# KT-744.net
KiCad netlist of a schematic drawn in EAGLE
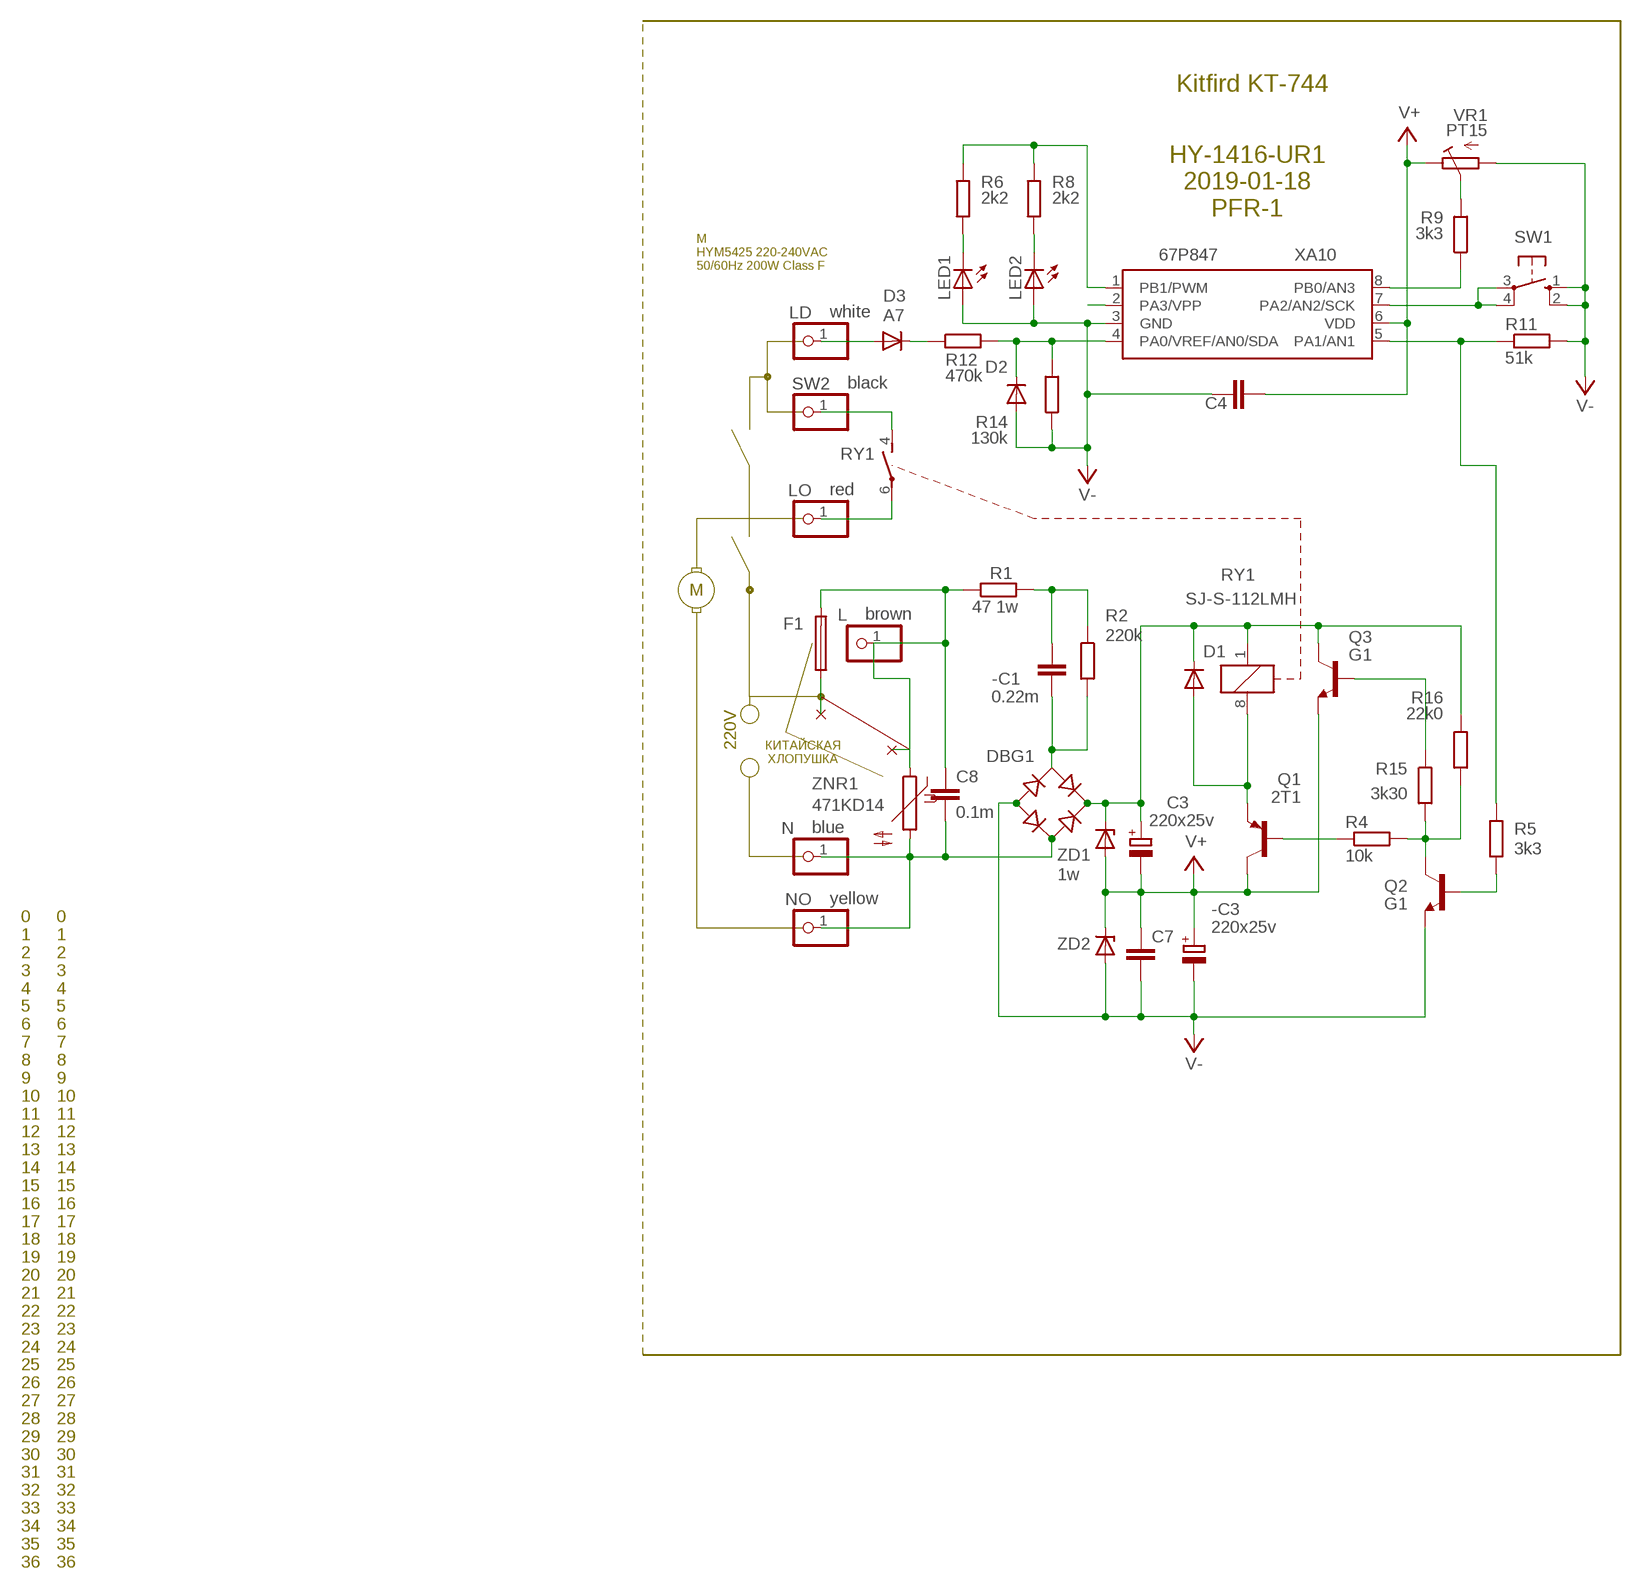
[diagram p0: schematic, sheet 1]

(export (version "E")
  (design (tool "Eeschema 10.0.6"))
  (components
    (comp (ref "-C1")
      (value "0.22m")
      (footprint "eagle-import:C150-072X183")
      (libsource (lib "eagle-import") (part "C-EU150-072X183"))
    )
    (comp (ref "-C3")
      (value "220x25v")
      (footprint "eagle-import:E5-10,5")
      (libsource (lib "eagle-import") (part "CPOL-EUE5-10.5"))
    )
    (comp (ref "67P847")
      (value "XA10")
      (footprint "eagle-import:SOIC8")
      (libsource (lib "eagle-import") (part "SH67P847"))
    )
    (comp (ref "C3")
      (value "220x25v")
      (footprint "eagle-import:E5-10,5")
      (libsource (lib "eagle-import") (part "CPOL-EUE5-10.5"))
    )
    (comp (ref "C4")
      (value "C-EU150-072X183")
      (footprint "eagle-import:C150-072X183")
      (libsource (lib "eagle-import") (part "C-EU150-072X183"))
    )
    (comp (ref "C7")
      (value "C-EU150-072X183")
      (footprint "eagle-import:C150-072X183")
      (libsource (lib "eagle-import") (part "C-EU150-072X183"))
    )
    (comp (ref "C8")
      (value "0.1m")
      (footprint "eagle-import:C102-064X133")
      (libsource (lib "eagle-import") (part "C-EU102-064X133"))
    )
    (comp (ref "D1")
      (value "DIODE-SOD80C")
      (footprint "eagle-import:SOD80C")
      (libsource (lib "eagle-import") (part "DIODE-SOD80C"))
    )
    (comp (ref "D2")
      (value "DIODE-SOD80C")
      (footprint "eagle-import:SOD80C")
      (libsource (lib "eagle-import") (part "DIODE-SOD80C"))
    )
    (comp (ref "D3")
      (value "A7")
      (footprint "eagle-import:SOD80C")
      (libsource (lib "eagle-import") (part "DIODE-SOD80C"))
    )
    (comp (ref "DBG1")
      (value "B1S")
      (footprint "eagle-import:MBS")
      (libsource (lib "eagle-import") (part "BS1"))
    )
    (comp (ref "F1")
      (value "PICOFUSE")
      (footprint "eagle-import:PICOFUSE")
      (libsource (lib "eagle-import") (part "PICOFUSE"))
    )
    (comp (ref "L")
      (value "brown")
      (footprint "eagle-import:1X01")
      (libsource (lib "eagle-import") (part "PINHD-1X1"))
    )
    (comp (ref "LD")
      (value "white")
      (footprint "eagle-import:1X01")
      (libsource (lib "eagle-import") (part "PINHD-1X1"))
    )
    (comp (ref "LED1")
      (value "LEDSML0805")
      (footprint "eagle-import:SML0805")
      (libsource (lib "eagle-import") (part "LEDSML0805"))
    )
    (comp (ref "LED2")
      (value "LEDSML0805")
      (footprint "eagle-import:SML0805")
      (libsource (lib "eagle-import") (part "LEDSML0805"))
    )
    (comp (ref "LO")
      (value "red")
      (footprint "eagle-import:1X01")
      (libsource (lib "eagle-import") (part "PINHD-1X1"))
    )
    (comp (ref "N")
      (value "blue")
      (footprint "eagle-import:1X01")
      (libsource (lib "eagle-import") (part "PINHD-1X1"))
    )
    (comp (ref "NO")
      (value "yellow")
      (footprint "eagle-import:1X01")
      (libsource (lib "eagle-import") (part "PINHD-1X1"))
    )
    (comp (ref "Q1")
      (value "2T1")
      (footprint "eagle-import:SOT23-EBC")
      (libsource (lib "eagle-import") (part "-PNP-SOT23-EBC"))
    )
    (comp (ref "Q2")
      (value "G1")
      (footprint "eagle-import:SOT23-EBC")
      (libsource (lib "eagle-import") (part "-NPN-SOT23-EBC"))
    )
    (comp (ref "Q3")
      (value "G1")
      (footprint "eagle-import:SOT23-EBC")
      (libsource (lib "eagle-import") (part "-NPN-SOT23-EBC"))
    )
    (comp (ref "R1")
      (value "47 1w")
      (footprint "eagle-import:0414_15")
      (libsource (lib "eagle-import") (part "R-EU_0414/15"))
    )
    (comp (ref "R2")
      (value "220k")
      (footprint "eagle-import:0207_12")
      (libsource (lib "eagle-import") (part "R-EU_0207/12"))
    )
    (comp (ref "R4")
      (value "10k")
      (footprint "eagle-import:M1206")
      (libsource (lib "eagle-import") (part "R-EU_M1206"))
    )
    (comp (ref "R5")
      (value "3k3")
      (footprint "eagle-import:M0805")
      (libsource (lib "eagle-import") (part "R-EU_M0805"))
    )
    (comp (ref "R6")
      (value "2k2")
      (footprint "eagle-import:0207_12")
      (libsource (lib "eagle-import") (part "R-EU_0207/12"))
    )
    (comp (ref "R8")
      (value "2k2")
      (footprint "eagle-import:0207_12")
      (libsource (lib "eagle-import") (part "R-EU_0207/12"))
    )
    (comp (ref "R9")
      (value "3k3")
      (footprint "eagle-import:M0805")
      (libsource (lib "eagle-import") (part "R-EU_M0805"))
    )
    (comp (ref "R11")
      (value "51k")
      (footprint "eagle-import:M0805")
      (libsource (lib "eagle-import") (part "R-EU_M0805"))
    )
    (comp (ref "R12")
      (value "470k")
      (footprint "eagle-import:0207_15")
      (libsource (lib "eagle-import") (part "R-EU_0207/15"))
    )
    (comp (ref "R14")
      (value "130k")
      (footprint "eagle-import:M0805")
      (libsource (lib "eagle-import") (part "R-EU_M0805"))
    )
    (comp (ref "R15")
      (value "3k30")
      (footprint "eagle-import:M1206")
      (libsource (lib "eagle-import") (part "R-EU_M1206"))
    )
    (comp (ref "R16")
      (value "22k0")
      (footprint "eagle-import:M0805")
      (libsource (lib "eagle-import") (part "R-EU_M0805"))
    )
    (comp (ref "RY1")
      (value "SJ-S-112LMH")
      (footprint "eagle-import:JW1A")
      (libsource (lib "eagle-import") (part "JW1A"))
    )
    (comp (ref "SW1")
      (value "10-XX")
      (footprint "eagle-import:B3F-10XX")
      (fields (field (name "MPN") "B3F-1000"))
      (libsource (lib "eagle-import") (part "10-XX"))
    )
    (comp (ref "SW2")
      (value "black")
      (footprint "eagle-import:1X01")
      (libsource (lib "eagle-import") (part "PINHD-1X1"))
    )
    (comp (ref "VR1")
      (value "PT15")
      (footprint "eagle-import:RTRIM3339P")
      (libsource (lib "eagle-import") (part "R-TRIMM3339P"))
    )
    (comp (ref "ZD1")
      (value "1w")
      (footprint "eagle-import:F126Z10")
      (libsource (lib "eagle-import") (part "ZENER-DIODEF126-10"))
    )
    (comp (ref "ZD2")
      (value "ZENER-DIODEC1702-15")
      (footprint "eagle-import:C1702-15")
      (libsource (lib "eagle-import") (part "ZENER-DIODEC1702-15"))
    )
    (comp (ref "ZNR1")
      (value "471KD14")
      (footprint "eagle-import:S07K17")
      (libsource (lib "eagle-import") (part "S07K17"))
    )
  )
  (nets
    (net (code "1") (name "Net-(-C1-Pad1)") (class "Default")
      (node (ref "-C1") (pin "1") (pinfunction "1_1") (pintype "passive"))
      (node (ref "R1") (pin "2") (pinfunction "2_2") (pintype "passive"))
      (node (ref "R2") (pin "1") (pinfunction "1_1") (pintype "passive"))
    )
    (net (code "2") (name "Net-(-C1-Pad2)") (class "Default")
      (node (ref "-C1") (pin "2") (pinfunction "2_2") (pintype "passive"))
      (node (ref "DBG1") (pin "AC1") (pinfunction "AC1_AC1") (pintype "passive"))
      (node (ref "R2") (pin "2") (pinfunction "2_2") (pintype "passive"))
    )
    (net (code "3") (name "Net-(67P847-PA0{slash}VREF{slash}AN0{slash}SDA)") (class "Default")
      (node (ref "67P847") (pin "4") (pinfunction "PA0/VREF/AN0/SDA_4") (pintype "bidirectional"))
      (node (ref "D2") (pin "C") (pinfunction "C_C") (pintype "passive"))
      (node (ref "R12") (pin "2") (pinfunction "2_2") (pintype "passive"))
      (node (ref "R14") (pin "2") (pinfunction "2_2") (pintype "passive"))
    )
    (net (code "4") (name "Net-(67P847-PA1{slash}AN1)") (class "Default")
      (node (ref "67P847") (pin "5") (pinfunction "PA1/AN1_5") (pintype "bidirectional"))
      (node (ref "R11") (pin "1") (pinfunction "1_1") (pintype "passive"))
      (node (ref "R5") (pin "1") (pinfunction "1_1") (pintype "passive"))
    )
    (net (code "5") (name "Net-(67P847-PA2{slash}AN2{slash}SCK)") (class "Default")
      (node (ref "67P847") (pin "7") (pinfunction "PA2/AN2/SCK_7") (pintype "bidirectional"))
      (node (ref "SW1") (pin "3") (pinfunction "P_3") (pintype "passive"))
      (node (ref "SW1") (pin "4") (pinfunction "P1_4") (pintype "passive"))
    )
    (net (code "6") (name "Net-(67P847-PB0{slash}AN3)") (class "Default")
      (node (ref "67P847") (pin "8") (pinfunction "PB0/AN3_8") (pintype "bidirectional"))
      (node (ref "R9") (pin "1") (pinfunction "1_1") (pintype "passive"))
    )
    (net (code "7") (name "Net-(67P847-PB1{slash}PWM)") (class "Default")
      (node (ref "67P847") (pin "1") (pinfunction "PB1/PWM_1") (pintype "bidirectional"))
      (node (ref "R6") (pin "2") (pinfunction "2_2") (pintype "passive"))
      (node (ref "R8") (pin "2") (pinfunction "2_2") (pintype "passive"))
    )
    (net (code "8") (name "Net-(C3-Pad+)") (class "Default")
      (node (ref "C3") (pin "+") (pinfunction "+_+") (pintype "passive"))
      (node (ref "D1") (pin "C") (pinfunction "C_C") (pintype "passive"))
      (node (ref "DBG1") (pin "+") (pinfunction "+_+") (pintype "passive"))
      (node (ref "Q3") (pin "C") (pinfunction "C_C") (pintype "passive"))
      (node (ref "R16") (pin "1") (pinfunction "1_1") (pintype "passive"))
      (node (ref "RY1") (pin "1") (pinfunction "1_1") (pintype "passive"))
      (node (ref "ZD1") (pin "C") (pinfunction "C_C") (pintype "passive"))
    )
    (net (code "9") (name "Net-(C8-Pad1)") (class "Default")
      (node (ref "C8") (pin "1") (pinfunction "1_1") (pintype "passive"))
      (node (ref "F1") (pin "2") (pinfunction "2_2") (pintype "passive"))
      (node (ref "L") (pin "1") (pinfunction "1_1") (pintype "passive"))
      (node (ref "R1") (pin "1") (pinfunction "1_1") (pintype "passive"))
      (node (ref "ZNR1") (pin "1") (pinfunction "1_1") (pintype "passive"))
    )
    (net (code "10") (name "Net-(C8-Pad2)") (class "Default")
      (node (ref "C8") (pin "2") (pinfunction "2_2") (pintype "passive"))
      (node (ref "DBG1") (pin "AC2") (pinfunction "AC2_AC2") (pintype "passive"))
      (node (ref "N") (pin "1") (pinfunction "1_1") (pintype "passive"))
      (node (ref "NO") (pin "1") (pinfunction "1_1") (pintype "passive"))
      (node (ref "ZNR1") (pin "2") (pinfunction "2_2") (pintype "passive"))
    )
    (net (code "11") (name "Net-(D3-PadA)") (class "Default")
      (node (ref "D3") (pin "A") (pinfunction "A_A") (pintype "passive"))
      (node (ref "LD") (pin "1") (pinfunction "1_1") (pintype "passive"))
    )
    (net (code "12") (name "Net-(D3-PadC)") (class "Default")
      (node (ref "D3") (pin "C") (pinfunction "C_C") (pintype "passive"))
      (node (ref "R12") (pin "1") (pinfunction "1_1") (pintype "passive"))
    )
    (net (code "13") (name "Net-(LED1-PadC)") (class "Default")
      (node (ref "LED1") (pin "C") (pinfunction "C_C") (pintype "passive"))
      (node (ref "R6") (pin "1") (pinfunction "1_1") (pintype "passive"))
    )
    (net (code "14") (name "Net-(LED2-PadC)") (class "Default")
      (node (ref "LED2") (pin "C") (pinfunction "C_C") (pintype "passive"))
      (node (ref "R8") (pin "1") (pinfunction "1_1") (pintype "passive"))
    )
    (net (code "15") (name "Net-(Q1-PadB)") (class "Default")
      (node (ref "Q1") (pin "B") (pinfunction "B_B") (pintype "passive"))
      (node (ref "R4") (pin "1") (pinfunction "1_1") (pintype "passive"))
    )
    (net (code "16") (name "Net-(Q2-PadB)") (class "Default")
      (node (ref "Q2") (pin "B") (pinfunction "B_B") (pintype "passive"))
      (node (ref "R5") (pin "2") (pinfunction "2_2") (pintype "passive"))
    )
    (net (code "17") (name "Net-(Q2-PadC)") (class "Default")
      (node (ref "Q2") (pin "C") (pinfunction "C_C") (pintype "passive"))
      (node (ref "R15") (pin "2") (pinfunction "2_2") (pintype "passive"))
      (node (ref "R16") (pin "2") (pinfunction "2_2") (pintype "passive"))
      (node (ref "R4") (pin "2") (pinfunction "2_2") (pintype "passive"))
    )
    (net (code "18") (name "Net-(Q3-PadB)") (class "Default")
      (node (ref "Q3") (pin "B") (pinfunction "B_B") (pintype "passive"))
      (node (ref "R15") (pin "1") (pinfunction "1_1") (pintype "passive"))
    )
    (net (code "19") (name "Net-(RY1A-P)") (class "Default")
      (node (ref "LO") (pin "1") (pinfunction "1_1") (pintype "passive"))
      (node (ref "RY1") (pin "6") (pinfunction "P_6") (pintype "passive"))
    )
    (net (code "20") (name "Net-(RY1A-S)") (class "Default")
      (node (ref "RY1") (pin "4") (pinfunction "S_4") (pintype "passive"))
      (node (ref "SW2") (pin "1") (pinfunction "1_1") (pintype "passive"))
    )
    (net (code "21") (name "Net-(RY1B-2)") (class "Default")
      (node (ref "D1") (pin "A") (pinfunction "A_A") (pintype "passive"))
      (node (ref "Q1") (pin "E") (pinfunction "E_E") (pintype "passive"))
      (node (ref "RY1") (pin "8") (pinfunction "2_8") (pintype "passive"))
    )
    (net (code "22") (name "Net-(VR1-S)") (class "Default")
      (node (ref "R9") (pin "2") (pinfunction "2_2") (pintype "passive"))
      (node (ref "VR1") (pin "2") (pinfunction "S_2") (pintype "passive"))
    )
    (net (code "23") (name "V+") (class "Default")
      (node (ref "-C3") (pin "+") (pinfunction "+_+") (pintype "passive"))
      (node (ref "67P847") (pin "6") (pinfunction "VDD_6") (pintype "power_in"))
      (node (ref "C3") (pin "-") (pinfunction "-_-") (pintype "passive"))
      (node (ref "C4") (pin "2") (pinfunction "2_2") (pintype "passive"))
      (node (ref "C7") (pin "1") (pinfunction "1_1") (pintype "passive"))
      (node (ref "Q1") (pin "C") (pinfunction "C_C") (pintype "passive"))
      (node (ref "Q3") (pin "E") (pinfunction "E_E") (pintype "passive"))
      (node (ref "VR1") (pin "3") (pinfunction "E_3") (pintype "passive"))
      (node (ref "ZD1") (pin "A") (pinfunction "A_A") (pintype "passive"))
      (node (ref "ZD2") (pin "C") (pinfunction "C_C") (pintype "passive"))
    )
    (net (code "24") (name "V-") (class "Default")
      (node (ref "-C3") (pin "-") (pinfunction "-_-") (pintype "passive"))
      (node (ref "67P847") (pin "3") (pinfunction "GND_3") (pintype "power_in"))
      (node (ref "C4") (pin "1") (pinfunction "1_1") (pintype "passive"))
      (node (ref "C7") (pin "2") (pinfunction "2_2") (pintype "passive"))
      (node (ref "D2") (pin "A") (pinfunction "A_A") (pintype "passive"))
      (node (ref "DBG1") (pin "-") (pinfunction "-_-") (pintype "passive"))
      (node (ref "LED1") (pin "A") (pinfunction "A_A") (pintype "passive"))
      (node (ref "LED2") (pin "A") (pinfunction "A_A") (pintype "passive"))
      (node (ref "Q2") (pin "E") (pinfunction "E_E") (pintype "passive"))
      (node (ref "R11") (pin "2") (pinfunction "2_2") (pintype "passive"))
      (node (ref "R14") (pin "1") (pinfunction "1_1") (pintype "passive"))
      (node (ref "SW1") (pin "1") (pinfunction "S_1") (pintype "passive"))
      (node (ref "SW1") (pin "2") (pinfunction "S1_2") (pintype "passive"))
      (node (ref "VR1") (pin "1") (pinfunction "A_1") (pintype "passive"))
      (node (ref "ZD2") (pin "A") (pinfunction "A_A") (pintype "passive"))
    )
    (net (code "25") (name "unconnected-(67P847-PA3{slash}VPP-Pad2)") (class "Default")
      (node (ref "67P847") (pin "2") (pinfunction "PA3/VPP_2") (pintype "bidirectional"))
    )
    (net (code "26") (name "unconnected-(F1-Pad1)") (class "Default")
      (node (ref "F1") (pin "1") (pinfunction "1_1") (pintype "passive"))
    )
  )
)
